# USBOptoIso.net
KiCad netlist of a schematic drawn in EAGLE
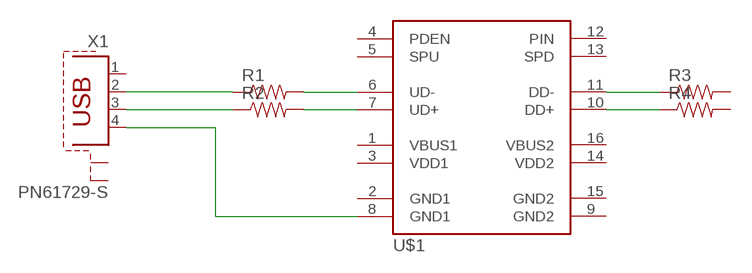
[diagram p0: schematic, sheet 1]

(export (version "E")
  (design (tool "Eeschema 10.0.6"))
  (components
    (comp (ref "R1")
      (value "RESISTORKIT")
      (footprint "eagle-import:AXIAL-0.3-KIT")
      (libsource (lib "eagle-import") (part "RESISTORKIT"))
    )
    (comp (ref "R2")
      (value "RESISTORKIT")
      (footprint "eagle-import:AXIAL-0.3-KIT")
      (libsource (lib "eagle-import") (part "RESISTORKIT"))
    )
    (comp (ref "R3")
      (value "RESISTORKIT")
      (footprint "eagle-import:AXIAL-0.3-KIT")
      (libsource (lib "eagle-import") (part "RESISTORKIT"))
    )
    (comp (ref "R4")
      (value "RESISTORKIT")
      (footprint "eagle-import:AXIAL-0.3-KIT")
      (libsource (lib "eagle-import") (part "RESISTORKIT"))
    )
    (comp (ref "U$1")
      (value "ADUM4160")
      (footprint "eagle-import:SO16W")
      (libsource (lib "eagle-import") (part "ADUM4160"))
    )
    (comp (ref "X1")
      (value "PN61729-S")
      (footprint "eagle-import:PN61729-S")
      (libsource (lib "eagle-import") (part "PN61729-S"))
    )
  )
  (nets
    (net (code "1") (name "/VBUS1") (class "Default")
      (node (ref "U$1") (pin "1") (pinfunction "VBUS1_1") (pintype "power_in"))
    )
    (net (code "2") (name "/VBUS2") (class "Default")
      (node (ref "U$1") (pin "16") (pinfunction "VBUS2_16") (pintype "power_in"))
    )
    (net (code "3") (name "/VDD1") (class "Default")
      (node (ref "U$1") (pin "3") (pinfunction "VDD1_3") (pintype "power_in"))
    )
    (net (code "4") (name "/VDD2") (class "Default")
      (node (ref "U$1") (pin "14") (pinfunction "VDD2_14") (pintype "power_in"))
    )
    (net (code "5") (name "Net-(R1-1)") (class "Default")
      (node (ref "R1") (pin "P$1") (pinfunction "1_P$1") (pintype "passive"))
      (node (ref "X1") (pin "2") (pinfunction "2_2") (pintype "passive"))
    )
    (net (code "6") (name "Net-(R1-2)") (class "Default")
      (node (ref "R1") (pin "P$2") (pinfunction "2_P$2") (pintype "passive"))
      (node (ref "U$1") (pin "6") (pinfunction "UD-_6") (pintype "bidirectional"))
    )
    (net (code "7") (name "Net-(R2-1)") (class "Default")
      (node (ref "R2") (pin "P$1") (pinfunction "1_P$1") (pintype "passive"))
      (node (ref "X1") (pin "3") (pinfunction "3_3") (pintype "passive"))
    )
    (net (code "8") (name "Net-(R2-2)") (class "Default")
      (node (ref "R2") (pin "P$2") (pinfunction "2_P$2") (pintype "passive"))
      (node (ref "U$1") (pin "7") (pinfunction "UD+_7") (pintype "bidirectional"))
    )
    (net (code "9") (name "Net-(R3-1)") (class "Default")
      (node (ref "R3") (pin "P$1") (pinfunction "1_P$1") (pintype "passive"))
      (node (ref "U$1") (pin "11") (pinfunction "DD-_11") (pintype "bidirectional"))
    )
    (net (code "10") (name "Net-(R4-1)") (class "Default")
      (node (ref "R4") (pin "P$1") (pinfunction "1_P$1") (pintype "passive"))
      (node (ref "U$1") (pin "10") (pinfunction "DD+_10") (pintype "bidirectional"))
    )
    (net (code "11") (name "Net-(U$1-GND1-Pad8)") (class "Default")
      (node (ref "U$1") (pin "8") (pinfunction "GND1_8") (pintype "passive"))
      (node (ref "X1") (pin "4") (pinfunction "4_4") (pintype "passive"))
    )
    (net (code "12") (name "unconnected-(R3-2-PadP$2)") (class "Default")
      (node (ref "R3") (pin "P$2") (pinfunction "2_P$2") (pintype "passive"))
    )
    (net (code "13") (name "unconnected-(R4-2-PadP$2)") (class "Default")
      (node (ref "R4") (pin "P$2") (pinfunction "2_P$2") (pintype "passive"))
    )
    (net (code "14") (name "unconnected-(U$1-GND1-Pad2)") (class "Default")
      (node (ref "U$1") (pin "2") (pinfunction "GND1_2") (pintype "passive"))
    )
    (net (code "15") (name "unconnected-(U$1-GND2-Pad9)") (class "Default")
      (node (ref "U$1") (pin "9") (pinfunction "GND2_9") (pintype "passive"))
    )
    (net (code "16") (name "unconnected-(U$1-GND2-Pad15)") (class "Default")
      (node (ref "U$1") (pin "15") (pinfunction "GND2_15") (pintype "passive"))
    )
    (net (code "17") (name "unconnected-(U$1-PDEN-Pad4)") (class "Default")
      (node (ref "U$1") (pin "4") (pinfunction "PDEN_4") (pintype "input"))
    )
    (net (code "18") (name "unconnected-(U$1-PIN-Pad12)") (class "Default")
      (node (ref "U$1") (pin "12") (pinfunction "PIN_12") (pintype "input"))
    )
    (net (code "19") (name "unconnected-(U$1-SPD-Pad13)") (class "Default")
      (node (ref "U$1") (pin "13") (pinfunction "SPD_13") (pintype "input"))
    )
    (net (code "20") (name "unconnected-(U$1-SPU-Pad5)") (class "Default")
      (node (ref "U$1") (pin "5") (pinfunction "SPU_5") (pintype "input"))
    )
    (net (code "21") (name "unconnected-(X1-Pad1)") (class "Default")
      (node (ref "X1") (pin "1") (pinfunction "1_1") (pintype "passive"))
    )
    (net (code "22") (name "unconnected-(X1-PadS1)") (class "Default")
      (node (ref "X1") (pin "S1") (pinfunction "S1_S1") (pintype "passive"))
    )
    (net (code "23") (name "unconnected-(X1-PadS2)") (class "Default")
      (node (ref "X1") (pin "S2") (pinfunction "S2_S2") (pintype "passive"))
    )
  )
)
